# JETSON_AGX_NVHS.net
KiCad netlist of a schematic drawn in Altium Designer
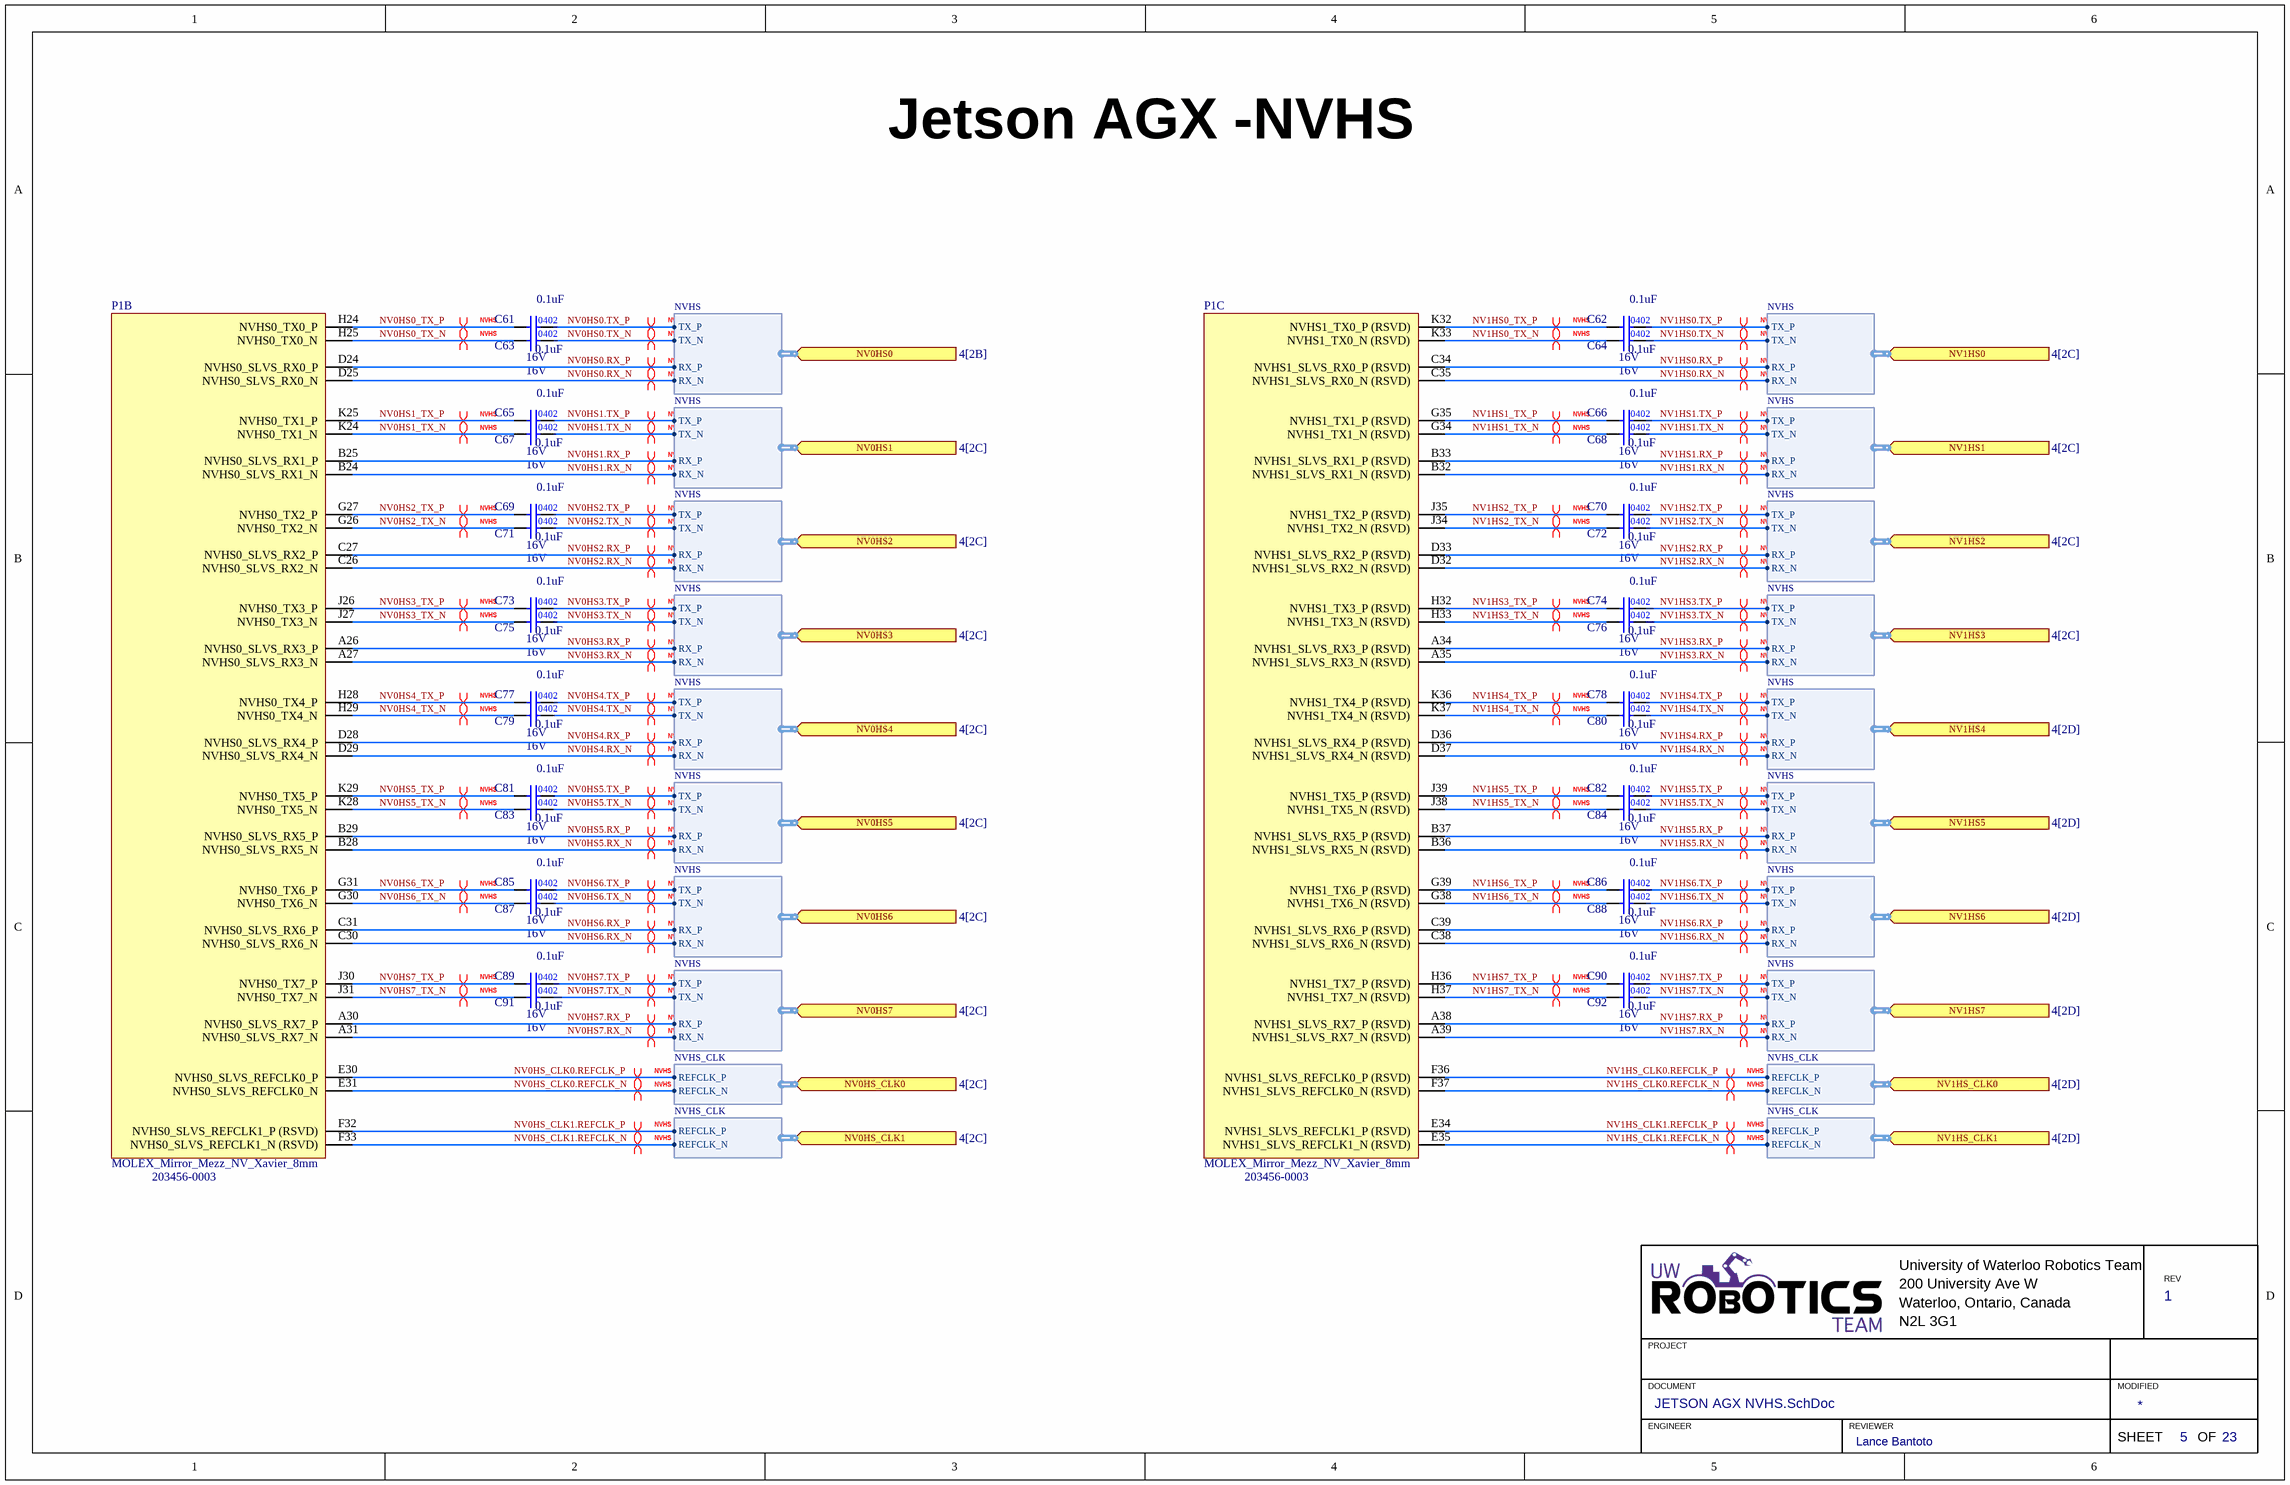
[diagram p0: JETSON AGX NVHS.SchDoc]

(export (version "E")
  (design (tool "Eeschema 10.0.6"))
  (components
    (comp (ref "C61")
      (value "CAP_0.1uF_16V_X7R_0402")
      (footprint "CAP0402")
      (description "CAP CER 0.1UF 16V X7R 0402")
      (fields (field (name "CAPACITANCE") "0.1uF") (field (name "VOLTAGE RATING") "16V"))
      (libsource (lib "UWRT_Schematic_Library_2020") (part "CAP_0.1uF_16V_X7R_0402"))
    )
    (comp (ref "C62")
      (value "CAP_0.1uF_16V_X7R_0402")
      (footprint "CAP0402")
      (description "CAP CER 0.1UF 16V X7R 0402")
      (fields (field (name "CAPACITANCE") "0.1uF") (field (name "VOLTAGE RATING") "16V"))
      (libsource (lib "UWRT_Schematic_Library_2020") (part "CAP_0.1uF_16V_X7R_0402"))
    )
    (comp (ref "C63")
      (value "CAP_0.1uF_16V_X7R_0402")
      (footprint "CAP0402")
      (description "CAP CER 0.1UF 16V X7R 0402")
      (fields (field (name "CAPACITANCE") "0.1uF") (field (name "VOLTAGE RATING") "16V"))
      (libsource (lib "UWRT_Schematic_Library_2020") (part "CAP_0.1uF_16V_X7R_0402"))
    )
    (comp (ref "C64")
      (value "CAP_0.1uF_16V_X7R_0402")
      (footprint "CAP0402")
      (description "CAP CER 0.1UF 16V X7R 0402")
      (fields (field (name "CAPACITANCE") "0.1uF") (field (name "VOLTAGE RATING") "16V"))
      (libsource (lib "UWRT_Schematic_Library_2020") (part "CAP_0.1uF_16V_X7R_0402"))
    )
    (comp (ref "C65")
      (value "CAP_0.1uF_16V_X7R_0402")
      (footprint "CAP0402")
      (description "CAP CER 0.1UF 16V X7R 0402")
      (fields (field (name "CAPACITANCE") "0.1uF") (field (name "VOLTAGE RATING") "16V"))
      (libsource (lib "UWRT_Schematic_Library_2020") (part "CAP_0.1uF_16V_X7R_0402"))
    )
    (comp (ref "C66")
      (value "CAP_0.1uF_16V_X7R_0402")
      (footprint "CAP0402")
      (description "CAP CER 0.1UF 16V X7R 0402")
      (fields (field (name "CAPACITANCE") "0.1uF") (field (name "VOLTAGE RATING") "16V"))
      (libsource (lib "UWRT_Schematic_Library_2020") (part "CAP_0.1uF_16V_X7R_0402"))
    )
    (comp (ref "C67")
      (value "CAP_0.1uF_16V_X7R_0402")
      (footprint "CAP0402")
      (description "CAP CER 0.1UF 16V X7R 0402")
      (fields (field (name "CAPACITANCE") "0.1uF") (field (name "VOLTAGE RATING") "16V"))
      (libsource (lib "UWRT_Schematic_Library_2020") (part "CAP_0.1uF_16V_X7R_0402"))
    )
    (comp (ref "C68")
      (value "CAP_0.1uF_16V_X7R_0402")
      (footprint "CAP0402")
      (description "CAP CER 0.1UF 16V X7R 0402")
      (fields (field (name "CAPACITANCE") "0.1uF") (field (name "VOLTAGE RATING") "16V"))
      (libsource (lib "UWRT_Schematic_Library_2020") (part "CAP_0.1uF_16V_X7R_0402"))
    )
    (comp (ref "C69")
      (value "CAP_0.1uF_16V_X7R_0402")
      (footprint "CAP0402")
      (description "CAP CER 0.1UF 16V X7R 0402")
      (fields (field (name "CAPACITANCE") "0.1uF") (field (name "VOLTAGE RATING") "16V"))
      (libsource (lib "UWRT_Schematic_Library_2020") (part "CAP_0.1uF_16V_X7R_0402"))
    )
    (comp (ref "C70")
      (value "CAP_0.1uF_16V_X7R_0402")
      (footprint "CAP0402")
      (description "CAP CER 0.1UF 16V X7R 0402")
      (fields (field (name "CAPACITANCE") "0.1uF") (field (name "VOLTAGE RATING") "16V"))
      (libsource (lib "UWRT_Schematic_Library_2020") (part "CAP_0.1uF_16V_X7R_0402"))
    )
    (comp (ref "C71")
      (value "CAP_0.1uF_16V_X7R_0402")
      (footprint "CAP0402")
      (description "CAP CER 0.1UF 16V X7R 0402")
      (fields (field (name "CAPACITANCE") "0.1uF") (field (name "VOLTAGE RATING") "16V"))
      (libsource (lib "UWRT_Schematic_Library_2020") (part "CAP_0.1uF_16V_X7R_0402"))
    )
    (comp (ref "C72")
      (value "CAP_0.1uF_16V_X7R_0402")
      (footprint "CAP0402")
      (description "CAP CER 0.1UF 16V X7R 0402")
      (fields (field (name "CAPACITANCE") "0.1uF") (field (name "VOLTAGE RATING") "16V"))
      (libsource (lib "UWRT_Schematic_Library_2020") (part "CAP_0.1uF_16V_X7R_0402"))
    )
    (comp (ref "C73")
      (value "CAP_0.1uF_16V_X7R_0402")
      (footprint "CAP0402")
      (description "CAP CER 0.1UF 16V X7R 0402")
      (fields (field (name "CAPACITANCE") "0.1uF") (field (name "VOLTAGE RATING") "16V"))
      (libsource (lib "UWRT_Schematic_Library_2020") (part "CAP_0.1uF_16V_X7R_0402"))
    )
    (comp (ref "C74")
      (value "CAP_0.1uF_16V_X7R_0402")
      (footprint "CAP0402")
      (description "CAP CER 0.1UF 16V X7R 0402")
      (fields (field (name "CAPACITANCE") "0.1uF") (field (name "VOLTAGE RATING") "16V"))
      (libsource (lib "UWRT_Schematic_Library_2020") (part "CAP_0.1uF_16V_X7R_0402"))
    )
    (comp (ref "C75")
      (value "CAP_0.1uF_16V_X7R_0402")
      (footprint "CAP0402")
      (description "CAP CER 0.1UF 16V X7R 0402")
      (fields (field (name "CAPACITANCE") "0.1uF") (field (name "VOLTAGE RATING") "16V"))
      (libsource (lib "UWRT_Schematic_Library_2020") (part "CAP_0.1uF_16V_X7R_0402"))
    )
    (comp (ref "C76")
      (value "CAP_0.1uF_16V_X7R_0402")
      (footprint "CAP0402")
      (description "CAP CER 0.1UF 16V X7R 0402")
      (fields (field (name "CAPACITANCE") "0.1uF") (field (name "VOLTAGE RATING") "16V"))
      (libsource (lib "UWRT_Schematic_Library_2020") (part "CAP_0.1uF_16V_X7R_0402"))
    )
    (comp (ref "C77")
      (value "CAP_0.1uF_16V_X7R_0402")
      (footprint "CAP0402")
      (description "CAP CER 0.1UF 16V X7R 0402")
      (fields (field (name "CAPACITANCE") "0.1uF") (field (name "VOLTAGE RATING") "16V"))
      (libsource (lib "UWRT_Schematic_Library_2020") (part "CAP_0.1uF_16V_X7R_0402"))
    )
    (comp (ref "C78")
      (value "CAP_0.1uF_16V_X7R_0402")
      (footprint "CAP0402")
      (description "CAP CER 0.1UF 16V X7R 0402")
      (fields (field (name "CAPACITANCE") "0.1uF") (field (name "VOLTAGE RATING") "16V"))
      (libsource (lib "UWRT_Schematic_Library_2020") (part "CAP_0.1uF_16V_X7R_0402"))
    )
    (comp (ref "C79")
      (value "CAP_0.1uF_16V_X7R_0402")
      (footprint "CAP0402")
      (description "CAP CER 0.1UF 16V X7R 0402")
      (fields (field (name "CAPACITANCE") "0.1uF") (field (name "VOLTAGE RATING") "16V"))
      (libsource (lib "UWRT_Schematic_Library_2020") (part "CAP_0.1uF_16V_X7R_0402"))
    )
    (comp (ref "C80")
      (value "CAP_0.1uF_16V_X7R_0402")
      (footprint "CAP0402")
      (description "CAP CER 0.1UF 16V X7R 0402")
      (fields (field (name "CAPACITANCE") "0.1uF") (field (name "VOLTAGE RATING") "16V"))
      (libsource (lib "UWRT_Schematic_Library_2020") (part "CAP_0.1uF_16V_X7R_0402"))
    )
    (comp (ref "C81")
      (value "CAP_0.1uF_16V_X7R_0402")
      (footprint "CAP0402")
      (description "CAP CER 0.1UF 16V X7R 0402")
      (fields (field (name "CAPACITANCE") "0.1uF") (field (name "VOLTAGE RATING") "16V"))
      (libsource (lib "UWRT_Schematic_Library_2020") (part "CAP_0.1uF_16V_X7R_0402"))
    )
    (comp (ref "C82")
      (value "CAP_0.1uF_16V_X7R_0402")
      (footprint "CAP0402")
      (description "CAP CER 0.1UF 16V X7R 0402")
      (fields (field (name "CAPACITANCE") "0.1uF") (field (name "VOLTAGE RATING") "16V"))
      (libsource (lib "UWRT_Schematic_Library_2020") (part "CAP_0.1uF_16V_X7R_0402"))
    )
    (comp (ref "C83")
      (value "CAP_0.1uF_16V_X7R_0402")
      (footprint "CAP0402")
      (description "CAP CER 0.1UF 16V X7R 0402")
      (fields (field (name "CAPACITANCE") "0.1uF") (field (name "VOLTAGE RATING") "16V"))
      (libsource (lib "UWRT_Schematic_Library_2020") (part "CAP_0.1uF_16V_X7R_0402"))
    )
    (comp (ref "C84")
      (value "CAP_0.1uF_16V_X7R_0402")
      (footprint "CAP0402")
      (description "CAP CER 0.1UF 16V X7R 0402")
      (fields (field (name "CAPACITANCE") "0.1uF") (field (name "VOLTAGE RATING") "16V"))
      (libsource (lib "UWRT_Schematic_Library_2020") (part "CAP_0.1uF_16V_X7R_0402"))
    )
    (comp (ref "C85")
      (value "CAP_0.1uF_16V_X7R_0402")
      (footprint "CAP0402")
      (description "CAP CER 0.1UF 16V X7R 0402")
      (fields (field (name "CAPACITANCE") "0.1uF") (field (name "VOLTAGE RATING") "16V"))
      (libsource (lib "UWRT_Schematic_Library_2020") (part "CAP_0.1uF_16V_X7R_0402"))
    )
    (comp (ref "C86")
      (value "CAP_0.1uF_16V_X7R_0402")
      (footprint "CAP0402")
      (description "CAP CER 0.1UF 16V X7R 0402")
      (fields (field (name "CAPACITANCE") "0.1uF") (field (name "VOLTAGE RATING") "16V"))
      (libsource (lib "UWRT_Schematic_Library_2020") (part "CAP_0.1uF_16V_X7R_0402"))
    )
    (comp (ref "C87")
      (value "CAP_0.1uF_16V_X7R_0402")
      (footprint "CAP0402")
      (description "CAP CER 0.1UF 16V X7R 0402")
      (fields (field (name "CAPACITANCE") "0.1uF") (field (name "VOLTAGE RATING") "16V"))
      (libsource (lib "UWRT_Schematic_Library_2020") (part "CAP_0.1uF_16V_X7R_0402"))
    )
    (comp (ref "C88")
      (value "CAP_0.1uF_16V_X7R_0402")
      (footprint "CAP0402")
      (description "CAP CER 0.1UF 16V X7R 0402")
      (fields (field (name "CAPACITANCE") "0.1uF") (field (name "VOLTAGE RATING") "16V"))
      (libsource (lib "UWRT_Schematic_Library_2020") (part "CAP_0.1uF_16V_X7R_0402"))
    )
    (comp (ref "C89")
      (value "CAP_0.1uF_16V_X7R_0402")
      (footprint "CAP0402")
      (description "CAP CER 0.1UF 16V X7R 0402")
      (fields (field (name "CAPACITANCE") "0.1uF") (field (name "VOLTAGE RATING") "16V"))
      (libsource (lib "UWRT_Schematic_Library_2020") (part "CAP_0.1uF_16V_X7R_0402"))
    )
    (comp (ref "C90")
      (value "CAP_0.1uF_16V_X7R_0402")
      (footprint "CAP0402")
      (description "CAP CER 0.1UF 16V X7R 0402")
      (fields (field (name "CAPACITANCE") "0.1uF") (field (name "VOLTAGE RATING") "16V"))
      (libsource (lib "UWRT_Schematic_Library_2020") (part "CAP_0.1uF_16V_X7R_0402"))
    )
    (comp (ref "C91")
      (value "CAP_0.1uF_16V_X7R_0402")
      (footprint "CAP0402")
      (description "CAP CER 0.1UF 16V X7R 0402")
      (fields (field (name "CAPACITANCE") "0.1uF") (field (name "VOLTAGE RATING") "16V"))
      (libsource (lib "UWRT_Schematic_Library_2020") (part "CAP_0.1uF_16V_X7R_0402"))
    )
    (comp (ref "C92")
      (value "CAP_0.1uF_16V_X7R_0402")
      (footprint "CAP0402")
      (description "CAP CER 0.1UF 16V X7R 0402")
      (fields (field (name "CAPACITANCE") "0.1uF") (field (name "VOLTAGE RATING") "16V"))
      (libsource (lib "UWRT_Schematic_Library_2020") (part "CAP_0.1uF_16V_X7R_0402"))
    )
    (comp (ref "P1")
      (value "MOLEX_Mirror_Mezz_NV_Xavier_8mm")
      (footprint "203456-0003")
      (description "CONN SELF-MATE 699POS SMD GOLD")
      (fields (field (name "MANUFACTURER PART NUMBER 1") "203456-0003"))
      (libsource (lib "UWRT_Schematic_Library_2020") (part "MOLEX_Mirror_Mezz_NV_Xavier_8mm"))
    )
  )
  (nets
    (net (code "3") (name "/NV0HS0.RX_N") (class "Default")
      (node (ref "P1") (pin "D25") (pinfunction "NVHS0_SLVS_RX0_N_D25") (pintype "passive"))
    )
    (net (code "4") (name "/NV0HS0.RX_P") (class "Default")
      (node (ref "P1") (pin "D24") (pinfunction "NVHS0_SLVS_RX0_P_D24") (pintype "passive"))
    )
    (net (code "5") (name "/NV0HS0.TX_N") (class "Default")
      (node (ref "C63") (pin "2") (pinfunction "2_2") (pintype "passive"))
    )
    (net (code "6") (name "/NV0HS0.TX_P") (class "Default")
      (node (ref "C61") (pin "2") (pinfunction "2_2") (pintype "passive"))
    )
    (net (code "7") (name "/NV0HS0_TX_N") (class "Default")
      (node (ref "C63") (pin "1") (pinfunction "1_1") (pintype "passive"))
      (node (ref "P1") (pin "H25") (pinfunction "NVHS0_TX0_N_H25") (pintype "passive"))
    )
    (net (code "8") (name "/NV0HS0_TX_P") (class "Default")
      (node (ref "C61") (pin "1") (pinfunction "1_1") (pintype "passive"))
      (node (ref "P1") (pin "H24") (pinfunction "NVHS0_TX0_P_H24") (pintype "passive"))
    )
    (net (code "9") (name "/NV0HS1.RX_N") (class "Default")
      (node (ref "P1") (pin "B24") (pinfunction "NVHS0_SLVS_RX1_N_B24") (pintype "passive"))
    )
    (net (code "10") (name "/NV0HS1.RX_P") (class "Default")
      (node (ref "P1") (pin "B25") (pinfunction "NVHS0_SLVS_RX1_P_B25") (pintype "passive"))
    )
    (net (code "11") (name "/NV0HS1.TX_N") (class "Default")
      (node (ref "C67") (pin "2") (pinfunction "2_2") (pintype "passive"))
    )
    (net (code "12") (name "/NV0HS1.TX_P") (class "Default")
      (node (ref "C65") (pin "2") (pinfunction "2_2") (pintype "passive"))
    )
    (net (code "13") (name "/NV0HS1_TX_N") (class "Default")
      (node (ref "C67") (pin "1") (pinfunction "1_1") (pintype "passive"))
      (node (ref "P1") (pin "K24") (pinfunction "NVHS0_TX1_N_K24") (pintype "passive"))
    )
    (net (code "14") (name "/NV0HS1_TX_P") (class "Default")
      (node (ref "C65") (pin "1") (pinfunction "1_1") (pintype "passive"))
      (node (ref "P1") (pin "K25") (pinfunction "NVHS0_TX1_P_K25") (pintype "passive"))
    )
    (net (code "15") (name "/NV0HS2.RX_N") (class "Default")
      (node (ref "P1") (pin "C26") (pinfunction "NVHS0_SLVS_RX2_N_C26") (pintype "passive"))
    )
    (net (code "16") (name "/NV0HS2.RX_P") (class "Default")
      (node (ref "P1") (pin "C27") (pinfunction "NVHS0_SLVS_RX2_P_C27") (pintype "passive"))
    )
    (net (code "17") (name "/NV0HS2.TX_N") (class "Default")
      (node (ref "C71") (pin "2") (pinfunction "2_2") (pintype "passive"))
    )
    (net (code "18") (name "/NV0HS2.TX_P") (class "Default")
      (node (ref "C69") (pin "2") (pinfunction "2_2") (pintype "passive"))
    )
    (net (code "19") (name "/NV0HS2_TX_N") (class "Default")
      (node (ref "C71") (pin "1") (pinfunction "1_1") (pintype "passive"))
      (node (ref "P1") (pin "G26") (pinfunction "NVHS0_TX2_N_G26") (pintype "passive"))
    )
    (net (code "20") (name "/NV0HS2_TX_P") (class "Default")
      (node (ref "C69") (pin "1") (pinfunction "1_1") (pintype "passive"))
      (node (ref "P1") (pin "G27") (pinfunction "NVHS0_TX2_P_G27") (pintype "passive"))
    )
    (net (code "21") (name "/NV0HS3.RX_N") (class "Default")
      (node (ref "P1") (pin "A27") (pinfunction "NVHS0_SLVS_RX3_N_A27") (pintype "passive"))
    )
    (net (code "22") (name "/NV0HS3.RX_P") (class "Default")
      (node (ref "P1") (pin "A26") (pinfunction "NVHS0_SLVS_RX3_P_A26") (pintype "passive"))
    )
    (net (code "23") (name "/NV0HS3.TX_N") (class "Default")
      (node (ref "C75") (pin "2") (pinfunction "2_2") (pintype "passive"))
    )
    (net (code "24") (name "/NV0HS3.TX_P") (class "Default")
      (node (ref "C73") (pin "2") (pinfunction "2_2") (pintype "passive"))
    )
    (net (code "25") (name "/NV0HS3_TX_N") (class "Default")
      (node (ref "C75") (pin "1") (pinfunction "1_1") (pintype "passive"))
      (node (ref "P1") (pin "J27") (pinfunction "NVHS0_TX3_N_J27") (pintype "passive"))
    )
    (net (code "26") (name "/NV0HS3_TX_P") (class "Default")
      (node (ref "C73") (pin "1") (pinfunction "1_1") (pintype "passive"))
      (node (ref "P1") (pin "J26") (pinfunction "NVHS0_TX3_P_J26") (pintype "passive"))
    )
    (net (code "27") (name "/NV0HS4.RX_N") (class "Default")
      (node (ref "P1") (pin "D29") (pinfunction "NVHS0_SLVS_RX4_N_D29") (pintype "passive"))
    )
    (net (code "28") (name "/NV0HS4.RX_P") (class "Default")
      (node (ref "P1") (pin "D28") (pinfunction "NVHS0_SLVS_RX4_P_D28") (pintype "passive"))
    )
    (net (code "29") (name "/NV0HS4.TX_N") (class "Default")
      (node (ref "C79") (pin "2") (pinfunction "2_2") (pintype "passive"))
    )
    (net (code "30") (name "/NV0HS4.TX_P") (class "Default")
      (node (ref "C77") (pin "2") (pinfunction "2_2") (pintype "passive"))
    )
    (net (code "31") (name "/NV0HS4_TX_N") (class "Default")
      (node (ref "C79") (pin "1") (pinfunction "1_1") (pintype "passive"))
      (node (ref "P1") (pin "H29") (pinfunction "NVHS0_TX4_N_H29") (pintype "passive"))
    )
    (net (code "32") (name "/NV0HS4_TX_P") (class "Default")
      (node (ref "C77") (pin "1") (pinfunction "1_1") (pintype "passive"))
      (node (ref "P1") (pin "H28") (pinfunction "NVHS0_TX4_P_H28") (pintype "passive"))
    )
    (net (code "33") (name "/NV0HS5.RX_N") (class "Default")
      (node (ref "P1") (pin "B28") (pinfunction "NVHS0_SLVS_RX5_N_B28") (pintype "passive"))
    )
    (net (code "34") (name "/NV0HS5.RX_P") (class "Default")
      (node (ref "P1") (pin "B29") (pinfunction "NVHS0_SLVS_RX5_P_B29") (pintype "passive"))
    )
    (net (code "35") (name "/NV0HS5.TX_N") (class "Default")
      (node (ref "C83") (pin "2") (pinfunction "2_2") (pintype "passive"))
    )
    (net (code "36") (name "/NV0HS5.TX_P") (class "Default")
      (node (ref "C81") (pin "2") (pinfunction "2_2") (pintype "passive"))
    )
    (net (code "37") (name "/NV0HS5_TX_N") (class "Default")
      (node (ref "C83") (pin "1") (pinfunction "1_1") (pintype "passive"))
      (node (ref "P1") (pin "K28") (pinfunction "NVHS0_TX5_N_K28") (pintype "passive"))
    )
    (net (code "38") (name "/NV0HS5_TX_P") (class "Default")
      (node (ref "C81") (pin "1") (pinfunction "1_1") (pintype "passive"))
      (node (ref "P1") (pin "K29") (pinfunction "NVHS0_TX5_P_K29") (pintype "passive"))
    )
    (net (code "39") (name "/NV0HS6.RX_N") (class "Default")
      (node (ref "P1") (pin "C30") (pinfunction "NVHS0_SLVS_RX6_N_C30") (pintype "passive"))
    )
    (net (code "40") (name "/NV0HS6.RX_P") (class "Default")
      (node (ref "P1") (pin "C31") (pinfunction "NVHS0_SLVS_RX6_P_C31") (pintype "passive"))
    )
    (net (code "41") (name "/NV0HS6.TX_N") (class "Default")
      (node (ref "C87") (pin "2") (pinfunction "2_2") (pintype "passive"))
    )
    (net (code "42") (name "/NV0HS6.TX_P") (class "Default")
      (node (ref "C85") (pin "2") (pinfunction "2_2") (pintype "passive"))
    )
    (net (code "43") (name "/NV0HS6_TX_N") (class "Default")
      (node (ref "C87") (pin "1") (pinfunction "1_1") (pintype "passive"))
      (node (ref "P1") (pin "G30") (pinfunction "NVHS0_TX6_N_G30") (pintype "passive"))
    )
    (net (code "44") (name "/NV0HS6_TX_P") (class "Default")
      (node (ref "C85") (pin "1") (pinfunction "1_1") (pintype "passive"))
      (node (ref "P1") (pin "G31") (pinfunction "NVHS0_TX6_P_G31") (pintype "passive"))
    )
    (net (code "45") (name "/NV0HS7.RX_N") (class "Default")
      (node (ref "P1") (pin "A31") (pinfunction "NVHS0_SLVS_RX7_N_A31") (pintype "passive"))
    )
    (net (code "46") (name "/NV0HS7.RX_P") (class "Default")
      (node (ref "P1") (pin "A30") (pinfunction "NVHS0_SLVS_RX7_P_A30") (pintype "passive"))
    )
    (net (code "47") (name "/NV0HS7.TX_N") (class "Default")
      (node (ref "C91") (pin "2") (pinfunction "2_2") (pintype "passive"))
    )
    (net (code "48") (name "/NV0HS7.TX_P") (class "Default")
      (node (ref "C89") (pin "2") (pinfunction "2_2") (pintype "passive"))
    )
    (net (code "49") (name "/NV0HS7_TX_N") (class "Default")
      (node (ref "C91") (pin "1") (pinfunction "1_1") (pintype "passive"))
      (node (ref "P1") (pin "J31") (pinfunction "NVHS0_TX7_N_J31") (pintype "passive"))
    )
    (net (code "50") (name "/NV0HS7_TX_P") (class "Default")
      (node (ref "C89") (pin "1") (pinfunction "1_1") (pintype "passive"))
      (node (ref "P1") (pin "J30") (pinfunction "NVHS0_TX7_P_J30") (pintype "passive"))
    )
    (net (code "51") (name "/NV0HS_CLK0.REFCLK_N") (class "Default")
      (node (ref "P1") (pin "E31") (pinfunction "NVHS0_SLVS_REFCLK0_N_E31") (pintype "passive"))
    )
    (net (code "52") (name "/NV0HS_CLK0.REFCLK_P") (class "Default")
      (node (ref "P1") (pin "E30") (pinfunction "NVHS0_SLVS_REFCLK0_P_E30") (pintype "passive"))
    )
    (net (code "53") (name "/NV0HS_CLK1.REFCLK_N") (class "Default")
      (node (ref "P1") (pin "F33") (pinfunction "NVHS0_SLVS_REFCLK1_N_(RSVD)_F33") (pintype "passive"))
    )
    (net (code "54") (name "/NV0HS_CLK1.REFCLK_P") (class "Default")
      (node (ref "P1") (pin "F32") (pinfunction "NVHS0_SLVS_REFCLK1_P_(RSVD)_F32") (pintype "passive"))
    )
    (net (code "55") (name "/NV1HS0.RX_N") (class "Default")
      (node (ref "P1") (pin "C35") (pinfunction "NVHS1_SLVS_RX0_N_(RSVD)_C35") (pintype "passive"))
    )
    (net (code "56") (name "/NV1HS0.RX_P") (class "Default")
      (node (ref "P1") (pin "C34") (pinfunction "NVHS1_SLVS_RX0_P_(RSVD)_C34") (pintype "passive"))
    )
    (net (code "57") (name "/NV1HS0.TX_N") (class "Default")
      (node (ref "C64") (pin "2") (pinfunction "2_2") (pintype "passive"))
    )
    (net (code "58") (name "/NV1HS0.TX_P") (class "Default")
      (node (ref "C62") (pin "2") (pinfunction "2_2") (pintype "passive"))
    )
    (net (code "59") (name "/NV1HS0_TX_N") (class "Default")
      (node (ref "C64") (pin "1") (pinfunction "1_1") (pintype "passive"))
      (node (ref "P1") (pin "K33") (pinfunction "NVHS1_TX0_N_(RSVD)_K33") (pintype "passive"))
    )
    (net (code "60") (name "/NV1HS0_TX_P") (class "Default")
      (node (ref "C62") (pin "1") (pinfunction "1_1") (pintype "passive"))
      (node (ref "P1") (pin "K32") (pinfunction "NVHS1_TX0_P_(RSVD)_K32") (pintype "passive"))
    )
    (net (code "61") (name "/NV1HS1.RX_N") (class "Default")
      (node (ref "P1") (pin "B32") (pinfunction "NVHS1_SLVS_RX1_N_(RSVD)_B32") (pintype "passive"))
    )
    (net (code "62") (name "/NV1HS1.RX_P") (class "Default")
      (node (ref "P1") (pin "B33") (pinfunction "NVHS1_SLVS_RX1_P_(RSVD)_B33") (pintype "passive"))
    )
    (net (code "63") (name "/NV1HS1.TX_N") (class "Default")
      (node (ref "C68") (pin "2") (pinfunction "2_2") (pintype "passive"))
    )
    (net (code "64") (name "/NV1HS1.TX_P") (class "Default")
      (node (ref "C66") (pin "2") (pinfunction "2_2") (pintype "passive"))
    )
    (net (code "65") (name "/NV1HS1_TX_N") (class "Default")
      (node (ref "C68") (pin "1") (pinfunction "1_1") (pintype "passive"))
      (node (ref "P1") (pin "G34") (pinfunction "NVHS1_TX1_N_(RSVD)_G34") (pintype "passive"))
    )
    (net (code "66") (name "/NV1HS1_TX_P") (class "Default")
      (node (ref "C66") (pin "1") (pinfunction "1_1") (pintype "passive"))
      (node (ref "P1") (pin "G35") (pinfunction "NVHS1_TX1_P_(RSVD)_G35") (pintype "passive"))
    )
    (net (code "67") (name "/NV1HS2.RX_N") (class "Default")
      (node (ref "P1") (pin "D32") (pinfunction "NVHS1_SLVS_RX2_N_(RSVD)_D32") (pintype "passive"))
    )
    (net (code "68") (name "/NV1HS2.RX_P") (class "Default")
      (node (ref "P1") (pin "D33") (pinfunction "NVHS1_SLVS_RX2_P_(RSVD)_D33") (pintype "passive"))
    )
    (net (code "69") (name "/NV1HS2.TX_N") (class "Default")
      (node (ref "C72") (pin "2") (pinfunction "2_2") (pintype "passive"))
    )
    (net (code "70") (name "/NV1HS2.TX_P") (class "Default")
      (node (ref "C70") (pin "2") (pinfunction "2_2") (pintype "passive"))
    )
    (net (code "71") (name "/NV1HS2_TX_N") (class "Default")
      (node (ref "C72") (pin "1") (pinfunction "1_1") (pintype "passive"))
      (node (ref "P1") (pin "J34") (pinfunction "NVHS1_TX2_N_(RSVD)_J34") (pintype "passive"))
    )
    (net (code "72") (name "/NV1HS2_TX_P") (class "Default")
      (node (ref "C70") (pin "1") (pinfunction "1_1") (pintype "passive"))
      (node (ref "P1") (pin "J35") (pinfunction "NVHS1_TX2_P_(RSVD)_J35") (pintype "passive"))
    )
    (net (code "73") (name "/NV1HS3.RX_N") (class "Default")
      (node (ref "P1") (pin "A35") (pinfunction "NVHS1_SLVS_RX3_N_(RSVD)_A35") (pintype "passive"))
    )
    (net (code "74") (name "/NV1HS3.RX_P") (class "Default")
      (node (ref "P1") (pin "A34") (pinfunction "NVHS1_SLVS_RX3_P_(RSVD)_A34") (pintype "passive"))
    )
    (net (code "75") (name "/NV1HS3.TX_N") (class "Default")
      (node (ref "C76") (pin "2") (pinfunction "2_2") (pintype "passive"))
    )
    (net (code "76") (name "/NV1HS3.TX_P") (class "Default")
      (node (ref "C74") (pin "2") (pinfunction "2_2") (pintype "passive"))
    )
    (net (code "77") (name "/NV1HS3_TX_N") (class "Default")
      (node (ref "C76") (pin "1") (pinfunction "1_1") (pintype "passive"))
      (node (ref "P1") (pin "H33") (pinfunction "NVHS1_TX3_N_(RSVD)_H33") (pintype "passive"))
    )
    (net (code "78") (name "/NV1HS3_TX_P") (class "Default")
      (node (ref "C74") (pin "1") (pinfunction "1_1") (pintype "passive"))
      (node (ref "P1") (pin "H32") (pinfunction "NVHS1_TX3_P_(RSVD)_H32") (pintype "passive"))
    )
    (net (code "79") (name "/NV1HS4.RX_N") (class "Default")
      (node (ref "P1") (pin "D37") (pinfunction "NVHS1_SLVS_RX4_N_(RSVD)_D37") (pintype "passive"))
    )
    (net (code "80") (name "/NV1HS4.RX_P") (class "Default")
      (node (ref "P1") (pin "D36") (pinfunction "NVHS1_SLVS_RX4_P_(RSVD)_D36") (pintype "passive"))
    )
    (net (code "81") (name "/NV1HS4.TX_N") (class "Default")
      (node (ref "C80") (pin "2") (pinfunction "2_2") (pintype "passive"))
    )
    (net (code "82") (name "/NV1HS4.TX_P") (class "Default")
      (node (ref "C78") (pin "2") (pinfunction "2_2") (pintype "passive"))
    )
    (net (code "83") (name "/NV1HS4_TX_N") (class "Default")
      (node (ref "C80") (pin "1") (pinfunction "1_1") (pintype "passive"))
      (node (ref "P1") (pin "K37") (pinfunction "NVHS1_TX4_N_(RSVD)_K37") (pintype "passive"))
    )
    (net (code "84") (name "/NV1HS4_TX_P") (class "Default")
      (node (ref "C78") (pin "1") (pinfunction "1_1") (pintype "passive"))
      (node (ref "P1") (pin "K36") (pinfunction "NVHS1_TX4_P_(RSVD)_K36") (pintype "passive"))
    )
    (net (code "85") (name "/NV1HS5.RX_N") (class "Default")
      (node (ref "P1") (pin "B36") (pinfunction "NVHS1_SLVS_RX5_N_(RSVD)_B36") (pintype "passive"))
    )
    (net (code "86") (name "/NV1HS5.RX_P") (class "Default")
      (node (ref "P1") (pin "B37") (pinfunction "NVHS1_SLVS_RX5_P_(RSVD)_B37") (pintype "passive"))
    )
    (net (code "87") (name "/NV1HS5.TX_N") (class "Default")
      (node (ref "C84") (pin "2") (pinfunction "2_2") (pintype "passive"))
    )
    (net (code "88") (name "/NV1HS5.TX_P") (class "Default")
      (node (ref "C82") (pin "2") (pinfunction "2_2") (pintype "passive"))
    )
    (net (code "89") (name "/NV1HS5_TX_N") (class "Default")
      (node (ref "C84") (pin "1") (pinfunction "1_1") (pintype "passive"))
      (node (ref "P1") (pin "J38") (pinfunction "NVHS1_TX5_N_(RSVD)_J38") (pintype "passive"))
    )
    (net (code "90") (name "/NV1HS5_TX_P") (class "Default")
      (node (ref "C82") (pin "1") (pinfunction "1_1") (pintype "passive"))
      (node (ref "P1") (pin "J39") (pinfunction "NVHS1_TX5_P_(RSVD)_J39") (pintype "passive"))
    )
    (net (code "91") (name "/NV1HS6.RX_N") (class "Default")
      (node (ref "P1") (pin "C38") (pinfunction "NVHS1_SLVS_RX6_N_(RSVD)_C38") (pintype "passive"))
    )
    (net (code "92") (name "/NV1HS6.RX_P") (class "Default")
      (node (ref "P1") (pin "C39") (pinfunction "NVHS1_SLVS_RX6_P_(RSVD)_C39") (pintype "passive"))
    )
    (net (code "93") (name "/NV1HS6.TX_N") (class "Default")
      (node (ref "C88") (pin "2") (pinfunction "2_2") (pintype "passive"))
    )
    (net (code "94") (name "/NV1HS6.TX_P") (class "Default")
      (node (ref "C86") (pin "2") (pinfunction "2_2") (pintype "passive"))
    )
    (net (code "95") (name "/NV1HS6_TX_N") (class "Default")
      (node (ref "C88") (pin "1") (pinfunction "1_1") (pintype "passive"))
      (node (ref "P1") (pin "G38") (pinfunction "NVHS1_TX6_N_(RSVD)_G38") (pintype "passive"))
    )
    (net (code "96") (name "/NV1HS6_TX_P") (class "Default")
      (node (ref "C86") (pin "1") (pinfunction "1_1") (pintype "passive"))
      (node (ref "P1") (pin "G39") (pinfunction "NVHS1_TX6_P_(RSVD)_G39") (pintype "passive"))
    )
    (net (code "97") (name "/NV1HS7.RX_N") (class "Default")
      (node (ref "P1") (pin "A39") (pinfunction "NVHS1_SLVS_RX7_N_(RSVD)_A39") (pintype "passive"))
    )
    (net (code "98") (name "/NV1HS7.RX_P") (class "Default")
      (node (ref "P1") (pin "A38") (pinfunction "NVHS1_SLVS_RX7_P_(RSVD)_A38") (pintype "passive"))
    )
    (net (code "99") (name "/NV1HS7.TX_N") (class "Default")
      (node (ref "C92") (pin "2") (pinfunction "2_2") (pintype "passive"))
    )
    (net (code "100") (name "/NV1HS7.TX_P") (class "Default")
      (node (ref "C90") (pin "2") (pinfunction "2_2") (pintype "passive"))
    )
    (net (code "101") (name "/NV1HS7_TX_N") (class "Default")
      (node (ref "C92") (pin "1") (pinfunction "1_1") (pintype "passive"))
      (node (ref "P1") (pin "H37") (pinfunction "NVHS1_TX7_N_(RSVD)_H37") (pintype "passive"))
    )
    (net (code "102") (name "/NV1HS7_TX_P") (class "Default")
      (node (ref "C90") (pin "1") (pinfunction "1_1") (pintype "passive"))
      (node (ref "P1") (pin "H36") (pinfunction "NVHS1_TX7_P_(RSVD)_H36") (pintype "passive"))
    )
    (net (code "103") (name "/NV1HS_CLK0.REFCLK_N") (class "Default")
      (node (ref "P1") (pin "F37") (pinfunction "NVHS1_SLVS_REFCLK0_N_(RSVD)_F37") (pintype "passive"))
    )
    (net (code "104") (name "/NV1HS_CLK0.REFCLK_P") (class "Default")
      (node (ref "P1") (pin "F36") (pinfunction "NVHS1_SLVS_REFCLK0_P_(RSVD)_F36") (pintype "passive"))
    )
    (net (code "105") (name "/NV1HS_CLK1.REFCLK_N") (class "Default")
      (node (ref "P1") (pin "E35") (pinfunction "NVHS1_SLVS_REFCLK1_N_(RSVD)_E35") (pintype "passive"))
    )
    (net (code "106") (name "/NV1HS_CLK1.REFCLK_P") (class "Default")
      (node (ref "P1") (pin "E34") (pinfunction "NVHS1_SLVS_REFCLK1_P_(RSVD)_E34") (pintype "passive"))
    )
  )
)
